# 01_POWER.net
KiCad netlist of a schematic drawn in Altium Designer
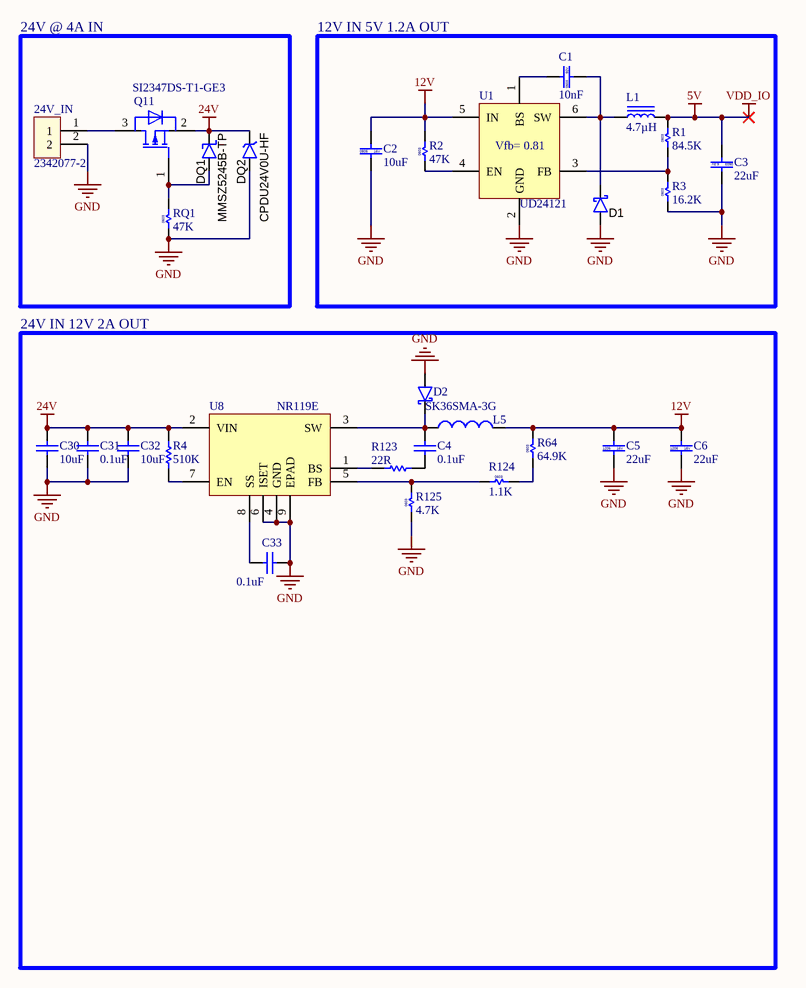
[diagram p0: 01_POWER.SchDoc]

(export (version "E")
  (design (tool "Eeschema 10.0.6"))
  (components
    (comp (ref "24V_IN")
      (value "2342077-2")
      (footprint "TERM BLOCK HDR 2POS 90DEG PITCH 3.81MM")
      (fields
        (field (name "DIGI-KEY PART NUMBER") "A145321-ND")
        (field (name "MANUFACTURER") "TE Connectivity AMP Connectors")
      )
      (libsource (lib "FKDZ_Altium_Lib") (part "TERM BLOCK HDR 2POS 90DEG 3.81MM"))
    )
    (comp (ref "C1")
      (value "10nF")
      (footprint "603C")
      (description "10nF ±5% 50V Ceramic Capacitor X7R 0603 (1608 Metric)")
      (fields (field (name "DIGI-KEY PART NUMBER") "311-1778-2-ND") (field (name "MANUFACTURER") "Yageo"))
      (libsource (lib "FKDZ_Altium_Lib") (part "CAP_CER_10nF_50V_%5_ X7R_ 0603"))
    )
    (comp (ref "C2")
      (value "10uF")
      (footprint "805C")
      (description "10µF ±10% 16V Ceramic Capacitor X6S 0805 (2012 Metric)")
      (fields
        (field (name "DIGI-KEY PART NUMBER") "490-5519-1-ND")
        (field (name "MANUFACTURER") "Murata Electronics North America")
      )
      (libsource (lib "FKDZ_Altium_Lib") (part "CAP_CER_10uF_16V_%10_ X5R_ 0805"))
    )
    (comp (ref "C3")
      (value "22uF")
      (footprint "603C")
      (description "22 µF ±20% 6.3V Ceramic Capacitor X5R 0603 (1608 Metric)")
      (fields
        (field (name "DIGI-KEY PART NUMBER") "2571-GMC10X5R226M6R3NTTR-ND")
        (field (name "MANUFACTURER") "CAL-CHIP ELECTRONICS, INC.")
      )
      (libsource (lib "FKDZ_Altium_Lib") (part "CAP CER 22UF 6.3V X5R 0603"))
    )
    (comp (ref "C4")
      (value "0.1uF")
      (footprint "603C")
      (description "0.1 µF ±10% 100V Ceramic Capacitor X7R 0603 (1608 Metric)")
      (fields
        (field (name "DIGI-KEY PART NUMBER") "2679-C0603X7R101-104KNPTR-ND")
        (field (name "MANUFACTURER") "Venkel")
      )
      (libsource (lib "FKDZ_Altium_Lib") (part "CAP CER 0.1UF 100V X7R 0603"))
    )
    (comp (ref "C5")
      (value "22uF")
      (footprint "1206C")
      (description "22µF ±20% 16V Ceramic Capacitor X5R 1206 (3216 Metric)")
      (fields
        (field (name "DIGI-KEY PART NUMBER") "1276-2728-1-ND")
        (field (name "MANUFACTURER") "Samsung Electro-Mechanics")
      )
      (libsource (lib "FKDZ_Altium_Lib") (part "CAP_CER_22uF_16V_%20_ X5R_ 1206"))
    )
    (comp (ref "C6")
      (value "22uF")
      (footprint "1206C")
      (description "22µF ±20% 16V Ceramic Capacitor X5R 1206 (3216 Metric)")
      (fields
        (field (name "DIGI-KEY PART NUMBER") "1276-2728-1-ND")
        (field (name "MANUFACTURER") "Samsung Electro-Mechanics")
      )
      (libsource (lib "FKDZ_Altium_Lib") (part "CAP_CER_22uF_16V_%20_ X5R_ 1206"))
    )
    (comp (ref "C30")
      (value "10uF")
      (footprint "1206C")
      (description "10µF ±20% 50V Ceramic Capacitor X5R 1206 (3216 Metric)")
      (fields
        (field (name "DIGI-KEY PART NUMBER") "1276-6736-1-ND")
        (field (name "MANUFACTURER") "Samsung Electro-Mechanics")
      )
      (libsource (lib "FKDZ_Altium_Lib") (part "CAP_CER_10uF_50V_%20_ X5R_ 1206"))
    )
    (comp (ref "C31")
      (value "0.1uF")
      (footprint "603C")
      (description "0.1 µF ±10% 100V Ceramic Capacitor X7R 0603 (1608 Metric)")
      (fields
        (field (name "DIGI-KEY PART NUMBER") "2679-C0603X7R101-104KNPTR-ND")
        (field (name "MANUFACTURER") "Venkel")
      )
      (libsource (lib "FKDZ_Altium_Lib") (part "CAP CER 0.1UF 100V X7R 0603"))
    )
    (comp (ref "C32")
      (value "10uF")
      (footprint "1206C")
      (description "10µF ±20% 50V Ceramic Capacitor X5R 1206 (3216 Metric)")
      (fields
        (field (name "DIGI-KEY PART NUMBER") "1276-6736-1-ND")
        (field (name "MANUFACTURER") "Samsung Electro-Mechanics")
      )
      (libsource (lib "FKDZ_Altium_Lib") (part "CAP_CER_10uF_50V_%20_ X5R_ 1206"))
    )
    (comp (ref "C33")
      (value "0.1uF")
      (footprint "603C")
      (description "0.1 µF ±10% 100V Ceramic Capacitor X7R 0603 (1608 Metric)")
      (fields
        (field (name "DIGI-KEY PART NUMBER") "2679-C0603X7R101-104KNPTR-ND")
        (field (name "MANUFACTURER") "Venkel")
      )
      (libsource (lib "FKDZ_Altium_Lib") (part "CAP CER 0.1UF 100V X7R 0603"))
    )
    (comp (ref "D1")
      (value "1N5819HW-7-F")
      (footprint "SOD123")
      (description "Diode Schottky 40V 1A Surface Mount SOD-123")
      (fields
        (field (name "MANUFACTURER") "Diodes Inc")
        (field (name "DIGI-KEY PART NUMBER") "1N5819HW-FDITR-ND")
      )
      (libsource (lib "FKDZ_Altium_Lib") (part "DIODE_SCHOTTKY_1N5819_1A_40V"))
    )
    (comp (ref "D2")
      (value "SK36SMA-3G")
      (footprint "DO-214AC")
      (description "Diode Schottky 60 V 3A Surface Mount SMA (DO-214AC)")
      (fields (field (name "DIGI-KEY PART NUMBER") "2796-SK36SMA-3GTR-ND"))
      (libsource (lib "FKDZ_Altium_Lib") (part "DIODE_SCHOTTKY SMA 60V 3A"))
    )
    (comp (ref "DQ1")
      (value "MMSZ5245B-TP")
      (footprint "SOD123")
      (description "Zener Diode 15 V 500 mW ±5% Surface Mount SOD-123")
      (fields
        (field (name "DIGI-KEY PART NUMBER") "MMSZ5245B-TPMSCT-ND")
        (field (name "MANUFACTURER") "Micro Commercial Co")
      )
      (libsource (lib "FKDZ_Altium_Lib") (part "DIODE ZENER 15V 500MW SOD123 MMSZ5245B-TP"))
    )
    (comp (ref "DQ2")
      (value "CPDU24V0U-HF")
      (footprint "SOD523F")
      (description "50V Clamp 3A (8/20µs) Ipp Tvs Diode Surface Mount 0603/SOD-523F")
      (fields
        (field (name "DIGI-KEY PART NUMBER") "641-1679-1-ND")
        (field (name "MANUFACTURER") "Comchip Technology")
      )
      (libsource (lib "FKDZ_Altium_Lib") (part "TVS DIODE 24VWM 50V 0603/SOD523F CPDU24V0U-HF"))
    )
    (comp (ref "L1")
      (value "4.7µH")
      (footprint "INDUCTOR 3mm 3mm")
      (description "4.7 µH Shielded Drum Core, Wirewound Inductor 1 A 120mOhm Max 1212 (3030 Metric)")
      (fields
        (field (name "DIGI-KEY PART NUMBER") "490-15954-1-ND")
        (field (name "MANUFACTURER") "Murata Electronics")
      )
      (libsource (lib "FKDZ_Altium_Lib") (part "FIXED IND 4.7UH 1A 120 MOHM 3mm x 3mm SMD LQH3NPN4R7MMEL"))
    )
    (comp (ref "L5")
      (value "10uH 2.4A 59.8mOhm")
      (footprint "inductor_SMD6x6mm")
      (description "10 µH Shielded Wirewound Inductor 2.4 A 59.8mOhm Max Nonstandard")
      (fields
        (field (name "MANUFACTURER") "Taiyo Yuden")
        (field (name "MANUFACTURER PART NUMBER") "NRS6045T100MMGK")
      )
      (libsource (lib "FKDZ_Altium_Lib") (part "FIXED IND 10UH 2.4A 59.8MOHM SMD"))
    )
    (comp (ref "Q11")
      (value "SI2347DS-T1-GE3")
      (footprint "SOT23-3")
      (description "P-Channel 30 V 5A (Tc) 1.7W (Tc) Surface Mount SOT-23-3 (TO-236)")
      (fields
        (field (name "DIGI-KEY PART NUMBER") "SI2347DS-T1-GE3CT-ND")
        (field (name "MANUFACTURER") "Vishay Siliconix")
      )
      (libsource (lib "FKDZ_Altium_Lib") (part "MOSFET P-CH 30V 5A SOT23-3 SI2347DS-T1-GE3"))
    )
    (comp (ref "R1")
      (value "84.5K")
      (footprint "603R")
      (description "84.5 kOhms ±1% 0.1W, 1/10W Chip Resistor 0603 (1608 Metric) Moisture Resistant Thick Film")
      (fields (field (name "DIGI-KEY PART NUMBER") "311-84.5KHRCT-ND") (field (name "MANUFACTURER") "Yageo"))
      (libsource (lib "FKDZ_Altium_Lib") (part "RES_84.5K_OHM_%1_0.1W_0603"))
    )
    (comp (ref "R2")
      (value "47K")
      (footprint "603R")
      (description "47 kOhms ±5% 0.1W, 1/10W Chip Resistor 0603 (1608 Metric) Moisture Resistant Thick Film")
      (fields (field (name "DIGI-KEY PART NUMBER") "311-47KGRTR-ND") (field (name "MANUFACTURER") "Yageo"))
      (libsource (lib "FKDZ_Altium_Lib") (part "RES_47K_OHM_%5_0.1W_0603"))
    )
    (comp (ref "R3")
      (value "16.2K")
      (footprint "603R")
      (description "16.2 kOhms ±1% 0.1W, 1/10W Chip Resistor 0603 (1608 Metric) Moisture Resistant Thick Film")
      (fields (field (name "DIGI-KEY PART NUMBER") "311-16.2KHRTR-ND") (field (name "MANUFACTURER") "Yageo"))
      (libsource (lib "FKDZ_Altium_Lib") (part "RES_16.2K_OHM_%1_0.1W_0603"))
    )
    (comp (ref "R4")
      (value "510K")
      (footprint "603R")
      (fields
        (field (name "DIGI-KEY PART NUMBER") "2019-RK73B1JTTD514JTR-ND")
        (field (name "MANUFACTURER") "KOA Speer Electronics, Inc.")
        (field (name "MANUFACTURER PART NUMBER") "RK73B1JTTD514J")
      )
      (libsource (lib "FKDZ_Altium_Lib") (part "RES 510K OHM 5% 1/10W 0603"))
    )
    (comp (ref "R64")
      (value "64.9K")
      (footprint "603R")
      (description "64.9 kOhms ±1% 0.1W, 1/10W Chip Resistor 0603 (1608 Metric) Moisture Resistant Thick Film")
      (fields (field (name "DIGI-KEY PART NUMBER") "311-64.9KHRCT-ND") (field (name "MANUFACTURER") "YAGEO"))
      (libsource (lib "FKDZ_Altium_Lib") (part "RES 64.9K OHM 1% 1/10W 0603"))
    )
    (comp (ref "R123")
      (value "22R")
      (footprint "603R")
      (description "22 Ohms ±5% 0.1W, 1/10W Chip Resistor 0603 (1608 Metric) Automotive AEC-Q200 Thick Film")
      (fields (field (name "DIGI-KEY PART NUMBER") "RMCF0603JT22R0TR-ND") (field (name "TOLERANCE") "±5%"))
      (libsource (lib "FKDZ_Altium_Lib") (part "RES_22 OHM 5% 1/10W 0603"))
    )
    (comp (ref "R124")
      (value "1.1K")
      (footprint "603R")
      (description "1.1 kOhms ±1% 0.1W, 1/10W Chip Resistor 0603 (1608 Metric) Moisture Resistant Thick Film")
      (fields (field (name "DIGI-KEY PART NUMBER") "311-1.10KHRCT-ND") (field (name "MANUFACTURER") "Yageo"))
      (libsource (lib "FKDZ_Altium_Lib") (part "RES_1.1K_OHM_%1_0.1W_0603"))
    )
    (comp (ref "R125")
      (value "4.7K")
      (footprint "603R")
      (description "4.7 kOhms ±1% 0.1W, 1/10W Chip Resistor 0603 (1608 Metric)  Thick Film")
      (fields (field (name "DIGI-KEY PART NUMBER") "311-4.70KHRCT-ND") (field (name "TOLERANCE") "±1%"))
      (libsource (lib "FKDZ_Altium_Lib") (part "RES SMD 4.7K OHM 1% 1/10W 0603"))
    )
    (comp (ref "RQ1")
      (value "47K")
      (footprint "603R")
      (description "47 kOhms ±5% 0.1W, 1/10W Chip Resistor 0603 (1608 Metric) Moisture Resistant Thick Film")
      (fields (field (name "DIGI-KEY PART NUMBER") "311-47KGRTR-ND") (field (name "MANUFACTURER") "Yageo"))
      (libsource (lib "FKDZ_Altium_Lib") (part "RES_47K_OHM_%5_0.1W_0603"))
    )
    (comp (ref "U1")
      (value "UD24121")
      (footprint "SOT-23-6L")
      (description "1.2A, 24V, 1.4MHz STEP-DOWN CONVERTER")
      (fields (field (name "MANUFACTURER") "UNISONIC TECHNOLOGIES CO., LTD"))
      (libsource (lib "FKDZ_Altium_Lib") (part "IC REG BUCK ADJ 1.2A SOT23-6 UD24121"))
    )
    (comp (ref "U8")
      (value "NR119E")
      (footprint "eSOIC8")
      (fields (field (name "DIGI-KEY PART NUMBER") "NR119ECT-ND") (field (name "MANUFACTURER") "Sanken"))
      (libsource (lib "FKDZ_Altium_Lib") (part "IC REG BUCK ADJUSTABLE 2A 8SOIC NR119E"))
    )
  )
  (nets
    (net (code "1") (name "5V") (class "Default")
      (node (ref "C3") (pin "2") (pinfunction "2_2") (pintype "passive"))
      (node (ref "L1") (pin "2") (pinfunction "2_2") (pintype "passive"))
      (node (ref "R1") (pin "2") (pinfunction "2_2") (pintype "passive"))
    )
    (net (code "2") (name "12V") (class "Default")
      (node (ref "C2") (pin "1") (pinfunction "1_1") (pintype "passive"))
      (node (ref "C5") (pin "1") (pinfunction "1_1") (pintype "passive"))
      (node (ref "C6") (pin "1") (pinfunction "1_1") (pintype "passive"))
      (node (ref "L5") (pin "2") (pinfunction "2_2") (pintype "passive"))
      (node (ref "R2") (pin "2") (pinfunction "2_2") (pintype "passive"))
      (node (ref "R64") (pin "2") (pinfunction "2_2") (pintype "passive"))
      (node (ref "U1") (pin "5") (pinfunction "IN_5") (pintype "power_in"))
    )
    (net (code "3") (name "24V") (class "Default")
      (node (ref "C30") (pin "2") (pinfunction "2_2") (pintype "passive"))
      (node (ref "C31") (pin "2") (pinfunction "2_2") (pintype "passive"))
      (node (ref "C32") (pin "2") (pinfunction "2_2") (pintype "passive"))
      (node (ref "DQ1") (pin "2") (pinfunction "K_2") (pintype "passive"))
      (node (ref "DQ2") (pin "2") (pinfunction "2_2") (pintype "passive"))
      (node (ref "Q11") (pin "2") (pinfunction "S_2") (pintype "passive"))
      (node (ref "R4") (pin "2") (pinfunction "2_2") (pintype "passive"))
      (node (ref "U8") (pin "2") (pinfunction "VIN_2") (pintype "power_in"))
    )
    (net (code "4") (name "GND") (class "Default")
      (node (ref "24V_IN") (pin "2") (pinfunction "2_2") (pintype "passive"))
      (node (ref "C2") (pin "2") (pinfunction "2_2") (pintype "passive"))
      (node (ref "C3") (pin "1") (pinfunction "1_1") (pintype "passive"))
      (node (ref "C30") (pin "1") (pinfunction "1_1") (pintype "passive"))
      (node (ref "C31") (pin "1") (pinfunction "1_1") (pintype "passive"))
      (node (ref "C32") (pin "1") (pinfunction "1_1") (pintype "passive"))
      (node (ref "C33") (pin "2") (pinfunction "2_2") (pintype "passive"))
      (node (ref "C5") (pin "2") (pinfunction "2_2") (pintype "passive"))
      (node (ref "C6") (pin "2") (pinfunction "2_2") (pintype "passive"))
      (node (ref "D1") (pin "1") (pinfunction "A_1") (pintype "passive"))
      (node (ref "D2") (pin "1") (pinfunction "A_1") (pintype "passive"))
      (node (ref "DQ2") (pin "1") (pinfunction "1_1") (pintype "passive"))
      (node (ref "R125") (pin "1") (pinfunction "1_1") (pintype "passive"))
      (node (ref "R3") (pin "1") (pinfunction "1_1") (pintype "passive"))
      (node (ref "RQ1") (pin "1") (pinfunction "1_1") (pintype "passive"))
      (node (ref "U1") (pin "2") (pinfunction "GND_2") (pintype "power_in"))
      (node (ref "U8") (pin "4") (pinfunction "GND_4") (pintype "power_in"))
      (node (ref "U8") (pin "6") (pinfunction "ISET_6") (pintype "passive"))
      (node (ref "U8") (pin "9") (pinfunction "EPAD_9") (pintype "power_in"))
    )
    (net (code "5") (name "Net-(C4-Pad2)") (class "Default")
      (node (ref "C4") (pin "2") (pinfunction "2_2") (pintype "passive"))
      (node (ref "R123") (pin "1") (pinfunction "1_1") (pintype "passive"))
    )
    (net (code "6") (name "Net-(D1-K)") (class "Default")
      (node (ref "C1") (pin "2") (pinfunction "2_2") (pintype "passive"))
      (node (ref "D1") (pin "2") (pinfunction "K_2") (pintype "passive"))
      (node (ref "L1") (pin "1") (pinfunction "1_1") (pintype "passive"))
      (node (ref "U1") (pin "6") (pinfunction "SW_6") (pintype "passive"))
    )
    (net (code "7") (name "Net-(D2-K)") (class "Default")
      (node (ref "C4") (pin "1") (pinfunction "1_1") (pintype "passive"))
      (node (ref "D2") (pin "2") (pinfunction "K_2") (pintype "passive"))
      (node (ref "L5") (pin "1") (pinfunction "1_1") (pintype "passive"))
      (node (ref "U8") (pin "3") (pinfunction "SW_3") (pintype "power_in"))
    )
    (net (code "8") (name "Net-(DQ1-A)") (class "Default")
      (node (ref "DQ1") (pin "1") (pinfunction "A_1") (pintype "passive"))
      (node (ref "Q11") (pin "1") (pinfunction "G_1") (pintype "passive"))
      (node (ref "RQ1") (pin "2") (pinfunction "2_2") (pintype "passive"))
    )
    (net (code "9") (name "Net-(Q11-D)") (class "Default")
      (node (ref "24V_IN") (pin "1") (pinfunction "1_1") (pintype "passive"))
      (node (ref "Q11") (pin "3") (pinfunction "D_3") (pintype "passive"))
    )
    (net (code "10") (name "Net-(R124-Pad2)") (class "Default")
      (node (ref "R124") (pin "2") (pinfunction "2_2") (pintype "passive"))
      (node (ref "R64") (pin "1") (pinfunction "1_1") (pintype "passive"))
    )
    (net (code "11") (name "Net-(U1-BS)") (class "Default")
      (node (ref "C1") (pin "1") (pinfunction "1_1") (pintype "passive"))
      (node (ref "U1") (pin "1") (pinfunction "BS_1") (pintype "passive"))
    )
    (net (code "12") (name "Net-(U1-EN)") (class "Default")
      (node (ref "R2") (pin "1") (pinfunction "1_1") (pintype "passive"))
      (node (ref "U1") (pin "4") (pinfunction "EN_4") (pintype "passive"))
    )
    (net (code "13") (name "Net-(U1-FB)") (class "Default")
      (node (ref "R1") (pin "1") (pinfunction "1_1") (pintype "passive"))
      (node (ref "R3") (pin "2") (pinfunction "2_2") (pintype "passive"))
      (node (ref "U1") (pin "3") (pinfunction "FB_3") (pintype "passive"))
    )
    (net (code "14") (name "Net-(U8-BS)") (class "Default")
      (node (ref "R123") (pin "2") (pinfunction "2_2") (pintype "passive"))
      (node (ref "U8") (pin "1") (pinfunction "BS_1") (pintype "passive"))
    )
    (net (code "15") (name "Net-(U8-EN)") (class "Default")
      (node (ref "R4") (pin "1") (pinfunction "1_1") (pintype "passive"))
      (node (ref "U8") (pin "7") (pinfunction "EN_7") (pintype "passive"))
    )
    (net (code "16") (name "Net-(U8-FB)") (class "Default")
      (node (ref "R124") (pin "1") (pinfunction "1_1") (pintype "passive"))
      (node (ref "R125") (pin "2") (pinfunction "2_2") (pintype "passive"))
      (node (ref "U8") (pin "5") (pinfunction "FB_5") (pintype "passive"))
    )
    (net (code "17") (name "Net-(U8-SS)") (class "Default")
      (node (ref "C33") (pin "1") (pinfunction "1_1") (pintype "passive"))
      (node (ref "U8") (pin "8") (pinfunction "SS_8") (pintype "passive"))
    )
  )
)
